# UV_Disinfection_Relay_Hw00.net
KiCad netlist of a schematic drawn in Altium Designer
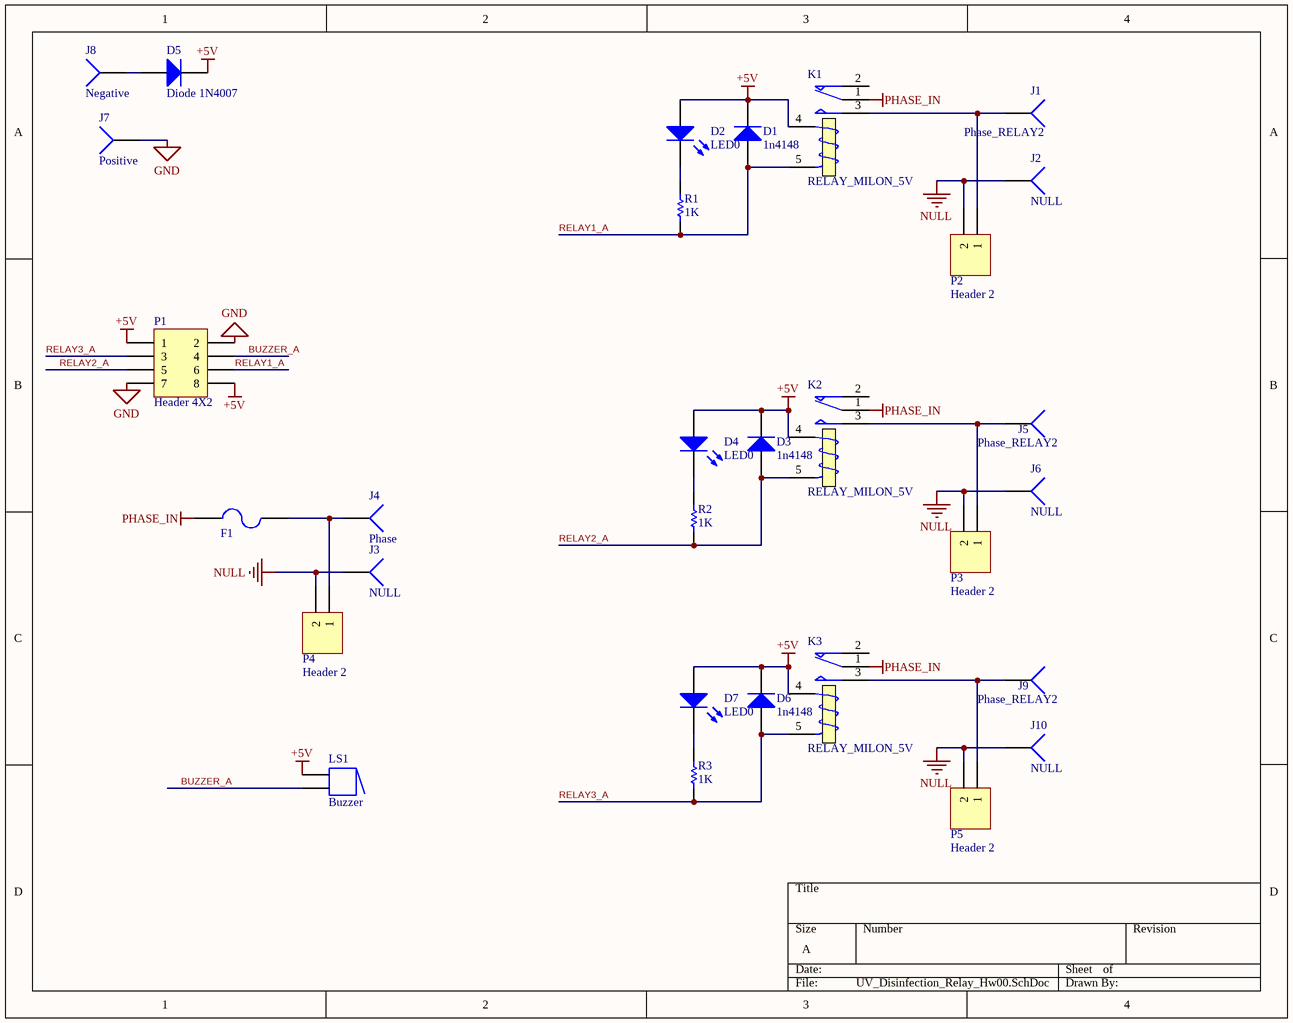
[diagram p0: UV_Disinfection_Relay_Hw00.SchDoc]

(export (version "E")
  (design (tool "Eeschema 10.0.6"))
  (components
    (comp (ref "D1")
      (value "1n4148")
      (footprint "DO 35")
      (description "1 Amp General Purpose Rectifier")
      (fields (field (name "PUBLISHER") "Altium Limited"))
      (libsource (lib "Miscellaneous Devices") (part "Diode 1N4007"))
    )
    (comp (ref "D2")
      (value "LED0")
      (footprint "LED5MM_GRN")
      (description "Typical INFRARED GaAs LED")
      (fields (field (name "PUBLISHER") "Altium Limited"))
      (libsource (lib "Miscellaneous Devices") (part "LED0"))
    )
    (comp (ref "D3")
      (value "1n4148")
      (footprint "DO 35")
      (description "1 Amp General Purpose Rectifier")
      (fields (field (name "PUBLISHER") "Altium Limited"))
      (libsource (lib "Miscellaneous Devices") (part "Diode 1N4007"))
    )
    (comp (ref "D4")
      (value "LED0")
      (footprint "LED5MM_GRN")
      (description "Typical INFRARED GaAs LED")
      (fields (field (name "PUBLISHER") "Altium Limited"))
      (libsource (lib "Miscellaneous Devices") (part "LED0"))
    )
    (comp (ref "D5")
      (value "Diode 1N4007")
      (footprint "DO-201AD - vertical")
      (description "1 Amp General Purpose Rectifier")
      (fields (field (name "PUBLISHER") "Altium Limited"))
      (libsource (lib "Miscellaneous Devices") (part "Diode 1N4007"))
    )
    (comp (ref "D6")
      (value "1n4148")
      (footprint "DO 35")
      (description "1 Amp General Purpose Rectifier")
      (fields (field (name "PUBLISHER") "Altium Limited"))
      (libsource (lib "Miscellaneous Devices") (part "Diode 1N4007"))
    )
    (comp (ref "D7")
      (value "LED0")
      (footprint "LED5MM_GRN")
      (description "Typical INFRARED GaAs LED")
      (fields (field (name "PUBLISHER") "Altium Limited"))
      (libsource (lib "Miscellaneous Devices") (part "LED0"))
    )
    (comp (ref "F1")
      (value "F=1.0 A")
      (footprint "Fuse 5x20")
      (description "Fuses 5x20")
      (fields (field (name "DESIGNER") "Abbas Basereh"))
      (libsource (lib "Mofidi3D") (part "Fuse 5x20 with holdeer pins"))
    )
    (comp (ref "J1")
      (value "Phase_RELAY2")
      (footprint "COOLER_TEMINAL_M_6.3mm")
      (description "Socket")
      (fields (field (name "PUBLISHER") "Altium Limited"))
      (libsource (lib "Miscellaneous Connectors") (part "Socket"))
    )
    (comp (ref "J2")
      (value "NULL")
      (footprint "COOLER_TEMINAL_M_6.3mm")
      (description "Socket")
      (fields (field (name "PUBLISHER") "Altium Limited"))
      (libsource (lib "Miscellaneous Connectors") (part "Socket"))
    )
    (comp (ref "J3")
      (value "NULL")
      (footprint "COOLER_TEMINAL_M_6.3mm")
      (description "Socket")
      (fields (field (name "PUBLISHER") "Altium Limited"))
      (libsource (lib "Miscellaneous Connectors") (part "Socket"))
    )
    (comp (ref "J4")
      (value "Phase")
      (footprint "COOLER_TEMINAL_M_6.3mm")
      (description "Socket")
      (fields (field (name "PUBLISHER") "Altium Limited"))
      (libsource (lib "Miscellaneous Connectors") (part "Socket"))
    )
    (comp (ref "J5")
      (value "Phase_RELAY2")
      (footprint "COOLER_TEMINAL_M_6.3mm")
      (description "Socket")
      (fields (field (name "PUBLISHER") "Altium Limited"))
      (libsource (lib "Miscellaneous Connectors") (part "Socket"))
    )
    (comp (ref "J6")
      (value "NULL")
      (footprint "COOLER_TEMINAL_M_6.3mm")
      (description "Socket")
      (fields (field (name "PUBLISHER") "Altium Limited"))
      (libsource (lib "Miscellaneous Connectors") (part "Socket"))
    )
    (comp (ref "J7")
      (value "Positive")
      (footprint "COOLER_TEMINAL_M_6.3mm")
      (description "Socket")
      (fields (field (name "PUBLISHER") "Altium Limited"))
      (libsource (lib "Miscellaneous Connectors") (part "Socket"))
    )
    (comp (ref "J8")
      (value "Negative")
      (footprint "COOLER_TEMINAL_M_6.3mm")
      (description "Socket")
      (fields (field (name "PUBLISHER") "Altium Limited"))
      (libsource (lib "Miscellaneous Connectors") (part "Socket"))
    )
    (comp (ref "J9")
      (value "Phase_RELAY2")
      (footprint "COOLER_TEMINAL_M_6.3mm")
      (description "Socket")
      (fields (field (name "PUBLISHER") "Altium Limited"))
      (libsource (lib "Miscellaneous Connectors") (part "Socket"))
    )
    (comp (ref "J10")
      (value "NULL")
      (footprint "COOLER_TEMINAL_M_6.3mm")
      (description "Socket")
      (fields (field (name "PUBLISHER") "Altium Limited"))
      (libsource (lib "Miscellaneous Connectors") (part "Socket"))
    )
    (comp (ref "K1")
      (value "RELAY_MILON_5V")
      (footprint "Relay 18.85x15.35x15.70")
      (description "RELAY 5V 7A 1C 5PIN")
      (fields (field (name "DESIGNER") "Abbas Basereh"))
      (libsource (lib "Mofidi3D") (part "Relay_SPDT"))
    )
    (comp (ref "K2")
      (value "RELAY_MILON_5V")
      (footprint "Relay 18.85x15.35x15.70")
      (description "RELAY 5V 7A 1C 5PIN")
      (fields (field (name "DESIGNER") "Abbas Basereh"))
      (libsource (lib "Mofidi3D") (part "Relay_SPDT"))
    )
    (comp (ref "K3")
      (value "RELAY_MILON_5V")
      (footprint "Relay 18.85x15.35x15.70")
      (description "RELAY 5V 7A 1C 5PIN")
      (fields (field (name "DESIGNER") "Abbas Basereh"))
      (libsource (lib "Mofidi3D") (part "Relay_SPDT"))
    )
    (comp (ref "LS1")
      (value "Buzzer")
      (footprint "BUZZER_12A05")
      (description "Magnetic Transducer Buzzer")
      (fields (field (name "PUBLISHER") "Altium Limited"))
      (libsource (lib "Miscellaneous Devices") (part "Buzzer"))
    )
    (comp (ref "P1")
      (value "Header 4X2")
      (footprint "HDR2X4")
      (description "Header, 4-Pin, Dual row")
      (fields (field (name "PUBLISHER") "Altium Limited"))
      (libsource (lib "Miscellaneous Connectors") (part "Header 4X2"))
    )
    (comp (ref "P2")
      (value "Header 2")
      (footprint "MSTB 2,5/2-G-5,08")
      (description "Header, 2-Pin")
      (fields (field (name "PUBLISHER") "Altium Limited"))
      (libsource (lib "Miscellaneous Connectors") (part "Header 2"))
    )
    (comp (ref "P3")
      (value "Header 2")
      (footprint "MSTB 2,5/2-G-5,08")
      (description "Header, 2-Pin")
      (fields (field (name "PUBLISHER") "Altium Limited"))
      (libsource (lib "Miscellaneous Connectors") (part "Header 2"))
    )
    (comp (ref "P4")
      (value "Header 2")
      (footprint "MSTB 2,5/2-G-5,08")
      (description "Header, 2-Pin")
      (fields (field (name "PUBLISHER") "Altium Limited"))
      (libsource (lib "Miscellaneous Connectors") (part "Header 2"))
    )
    (comp (ref "P5")
      (value "Header 2")
      (footprint "MSTB 2,5/2-G-5,08")
      (description "Header, 2-Pin")
      (fields (field (name "PUBLISHER") "Altium Limited"))
      (libsource (lib "Miscellaneous Connectors") (part "Header 2"))
    )
    (comp (ref "R1")
      (value "1K")
      (footprint "Axial 0_25w_2_54mm")
      (description "Resistor")
      (fields (field (name "PUBLISHER") "Altium Limited"))
      (libsource (lib "Miscellaneous Devices") (part "Res1"))
    )
    (comp (ref "R2")
      (value "1K")
      (footprint "Axial 0_25w_2_54mm")
      (description "Resistor")
      (fields (field (name "PUBLISHER") "Altium Limited"))
      (libsource (lib "Miscellaneous Devices") (part "Res1"))
    )
    (comp (ref "R3")
      (value "1K")
      (footprint "Axial 0_25w_2_54mm")
      (description "Resistor")
      (fields (field (name "PUBLISHER") "Altium Limited"))
      (libsource (lib "Miscellaneous Devices") (part "Res1"))
    )
  )
  (nets
    (net (code "1") (name "+5V") (class "Default")
      (node (ref "D1") (pin "2") (pinfunction "K_2") (pintype "passive"))
      (node (ref "D2") (pin "1") (pinfunction "A_1") (pintype "passive"))
      (node (ref "D3") (pin "2") (pinfunction "K_2") (pintype "passive"))
      (node (ref "D4") (pin "1") (pinfunction "A_1") (pintype "passive"))
      (node (ref "D5") (pin "2") (pinfunction "K_2") (pintype "passive"))
      (node (ref "D6") (pin "2") (pinfunction "K_2") (pintype "passive"))
      (node (ref "D7") (pin "1") (pinfunction "A_1") (pintype "passive"))
      (node (ref "K1") (pin "4") (pinfunction "T1_4") (pintype "passive"))
      (node (ref "K2") (pin "4") (pinfunction "T1_4") (pintype "passive"))
      (node (ref "K3") (pin "4") (pinfunction "T1_4") (pintype "passive"))
      (node (ref "LS1") (pin "1") (pinfunction "1_1") (pintype "passive"))
      (node (ref "P1") (pin "1") (pinfunction "1_1") (pintype "passive"))
      (node (ref "P1") (pin "8") (pinfunction "8_8") (pintype "passive"))
    )
    (net (code "2") (name "/BUZZER_A") (class "Default")
      (node (ref "LS1") (pin "2") (pinfunction "2_2") (pintype "passive"))
      (node (ref "P1") (pin "4") (pinfunction "4_4") (pintype "passive"))
    )
    (net (code "3") (name "/RELAY1_A") (class "Default")
      (node (ref "D1") (pin "1") (pinfunction "A_1") (pintype "passive"))
      (node (ref "K1") (pin "5") (pinfunction "T2_5") (pintype "passive"))
      (node (ref "P1") (pin "6") (pinfunction "6_6") (pintype "passive"))
      (node (ref "R1") (pin "1") (pinfunction "1_1") (pintype "passive"))
    )
    (net (code "4") (name "/RELAY2_A") (class "Default")
      (node (ref "D3") (pin "1") (pinfunction "A_1") (pintype "passive"))
      (node (ref "K2") (pin "5") (pinfunction "T2_5") (pintype "passive"))
      (node (ref "P1") (pin "5") (pinfunction "5_5") (pintype "passive"))
      (node (ref "R2") (pin "1") (pinfunction "1_1") (pintype "passive"))
    )
    (net (code "5") (name "/RELAY3_A") (class "Default")
      (node (ref "D6") (pin "1") (pinfunction "A_1") (pintype "passive"))
      (node (ref "K3") (pin "5") (pinfunction "T2_5") (pintype "passive"))
      (node (ref "P1") (pin "3") (pinfunction "3_3") (pintype "passive"))
      (node (ref "R3") (pin "1") (pinfunction "1_1") (pintype "passive"))
    )
    (net (code "6") (name "GND") (class "Default")
      (node (ref "J7") (pin "1") (pinfunction "1_1") (pintype "passive"))
      (node (ref "P1") (pin "2") (pinfunction "2_2") (pintype "passive"))
      (node (ref "P1") (pin "7") (pinfunction "7_7") (pintype "passive"))
    )
    (net (code "7") (name "NULL") (class "Default")
      (node (ref "J10") (pin "1") (pinfunction "1_1") (pintype "passive"))
      (node (ref "J2") (pin "1") (pinfunction "1_1") (pintype "passive"))
      (node (ref "J3") (pin "1") (pinfunction "1_1") (pintype "passive"))
      (node (ref "J6") (pin "1") (pinfunction "1_1") (pintype "passive"))
      (node (ref "P2") (pin "2") (pinfunction "2_2") (pintype "passive"))
      (node (ref "P3") (pin "2") (pinfunction "2_2") (pintype "passive"))
      (node (ref "P4") (pin "2") (pinfunction "2_2") (pintype "passive"))
      (node (ref "P5") (pin "2") (pinfunction "2_2") (pintype "passive"))
    )
    (net (code "8") (name "Net-(D2-K)") (class "Default")
      (node (ref "D2") (pin "2") (pinfunction "K_2") (pintype "passive"))
      (node (ref "R1") (pin "2") (pinfunction "2_2") (pintype "passive"))
    )
    (net (code "9") (name "Net-(D4-K)") (class "Default")
      (node (ref "D4") (pin "2") (pinfunction "K_2") (pintype "passive"))
      (node (ref "R2") (pin "2") (pinfunction "2_2") (pintype "passive"))
    )
    (net (code "10") (name "Net-(D5-A)") (class "Default")
      (node (ref "D5") (pin "1") (pinfunction "A_1") (pintype "passive"))
      (node (ref "J8") (pin "1") (pinfunction "1_1") (pintype "passive"))
    )
    (net (code "11") (name "Net-(D7-K)") (class "Default")
      (node (ref "D7") (pin "2") (pinfunction "K_2") (pintype "passive"))
      (node (ref "R3") (pin "2") (pinfunction "2_2") (pintype "passive"))
    )
    (net (code "12") (name "Net-(F1-Pad2)") (class "Default")
      (node (ref "F1") (pin "2") (pinfunction "2_2") (pintype "passive"))
      (node (ref "J4") (pin "1") (pinfunction "1_1") (pintype "passive"))
      (node (ref "P4") (pin "1") (pinfunction "1_1") (pintype "passive"))
    )
    (net (code "13") (name "Net-(K1-NO)") (class "Default")
      (node (ref "J1") (pin "1") (pinfunction "1_1") (pintype "passive"))
      (node (ref "K1") (pin "3") (pinfunction "NO_3") (pintype "passive"))
      (node (ref "P2") (pin "1") (pinfunction "1_1") (pintype "passive"))
    )
    (net (code "14") (name "Net-(K2-NO)") (class "Default")
      (node (ref "J5") (pin "1") (pinfunction "1_1") (pintype "passive"))
      (node (ref "K2") (pin "3") (pinfunction "NO_3") (pintype "passive"))
      (node (ref "P3") (pin "1") (pinfunction "1_1") (pintype "passive"))
    )
    (net (code "15") (name "Net-(K3-NO)") (class "Default")
      (node (ref "J9") (pin "1") (pinfunction "1_1") (pintype "passive"))
      (node (ref "K3") (pin "3") (pinfunction "NO_3") (pintype "passive"))
      (node (ref "P5") (pin "1") (pinfunction "1_1") (pintype "passive"))
    )
    (net (code "16") (name "PHASE_IN") (class "Default")
      (node (ref "F1") (pin "1") (pinfunction "1_1") (pintype "passive"))
      (node (ref "K1") (pin "1") (pinfunction "COM_1") (pintype "passive"))
      (node (ref "K2") (pin "1") (pinfunction "COM_1") (pintype "passive"))
      (node (ref "K3") (pin "1") (pinfunction "COM_1") (pintype "passive"))
    )
    (net (code "17") (name "unconnected-(K1-NC-Pad2)") (class "Default")
      (node (ref "K1") (pin "2") (pinfunction "NC_2") (pintype "passive"))
    )
    (net (code "18") (name "unconnected-(K2-NC-Pad2)") (class "Default")
      (node (ref "K2") (pin "2") (pinfunction "NC_2") (pintype "passive"))
    )
    (net (code "19") (name "unconnected-(K3-NC-Pad2)") (class "Default")
      (node (ref "K3") (pin "2") (pinfunction "NC_2") (pintype "passive"))
    )
  )
)
